# finalpcb_tz12_fp10.net
KiCad netlist of a schematic drawn in EAGLE
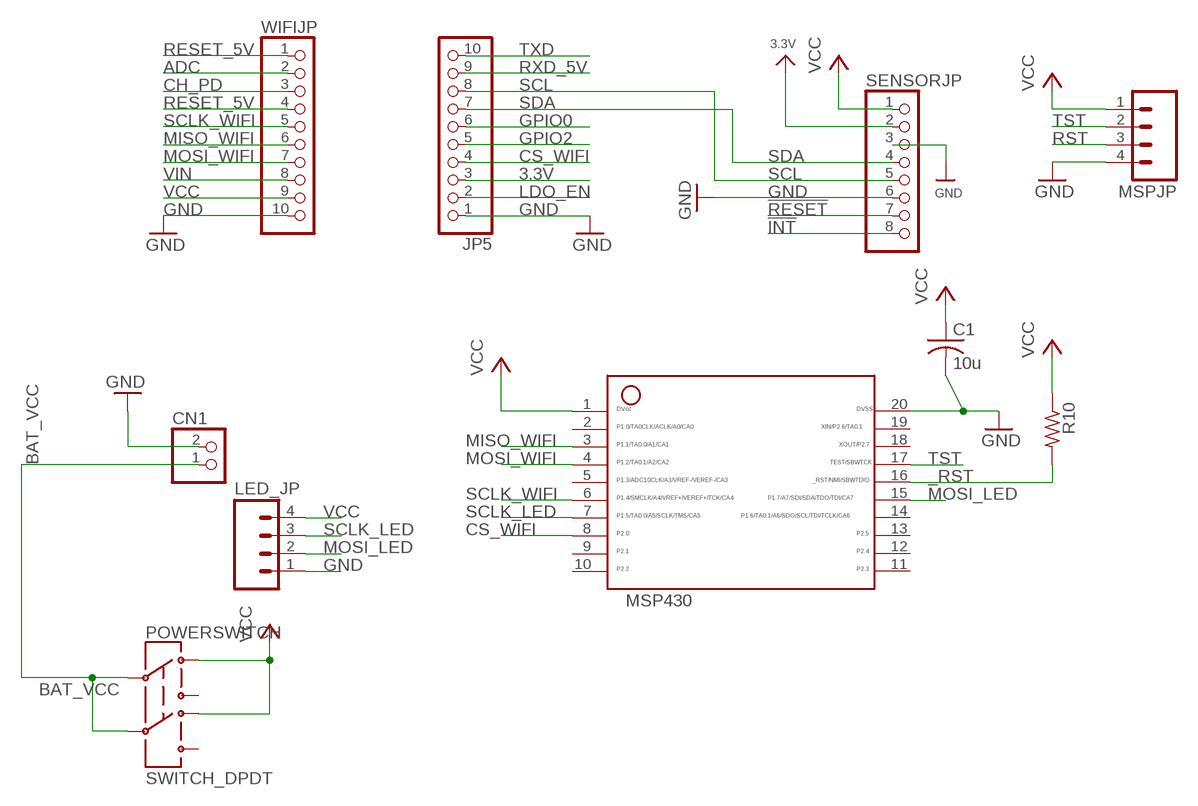
[diagram p0: schematic, sheet 1]

(export (version "E")
  (design (tool "Eeschema 10.0.6"))
  (components
    (comp (ref "C1")
      (value "10u")
      (footprint "eagle-import:C1206")
      (libsource (lib "eagle-import") (part "C-USC1206"))
    )
    (comp (ref "CN1")
      (value "JST_2PIN-SMT-RA")
      (footprint "eagle-import:JST-PH-2-SMT-RA")
      (libsource (lib "eagle-import") (part "JST_2PIN-SMT-RA"))
    )
    (comp (ref "JP5")
      (value "HEADER-1X1070MIL")
      (footprint "eagle-import:1X10_ROUND70")
      (libsource (lib "eagle-import") (part "HEADER-1X1070MIL"))
    )
    (comp (ref "LED_JP")
      (value "PENDANT_M04LOCK")
      (footprint "eagle-import:PENDANT_1X04_LOCK")
      (libsource (lib "eagle-import") (part "PENDANT_M04LOCK"))
    )
    (comp (ref "MSP430")
      (value "RATDBS_MSP430")
      (footprint "eagle-import:RATDBS_20_PIN")
      (libsource (lib "eagle-import") (part "RATDBS_MSP430"))
    )
    (comp (ref "MSPJP")
      (value "PENDANT_M04LOCK")
      (footprint "eagle-import:PENDANT_1X04_LOCK")
      (libsource (lib "eagle-import") (part "PENDANT_M04LOCK"))
    )
    (comp (ref "POWERSWITCH")
      (value "SWITCH_DPDT")
      (footprint "eagle-import:JS_DPDT_TH")
      (libsource (lib "eagle-import") (part "SWITCH_DPDT"))
    )
    (comp (ref "R10")
      (value "R-US_R1206")
      (footprint "eagle-import:R1206")
      (libsource (lib "eagle-import") (part "R-US_R1206"))
    )
    (comp (ref "SENSORJP")
      (value "HEADER-1X870MIL")
      (footprint "eagle-import:1X08_ROUND_70")
      (libsource (lib "eagle-import") (part "HEADER-1X870MIL"))
    )
    (comp (ref "WIFIJP")
      (value "HEADER-1X1070MIL")
      (footprint "eagle-import:1X10_ROUND70")
      (libsource (lib "eagle-import") (part "HEADER-1X1070MIL"))
    )
  )
  (nets
    (net (code "1") (name "/ADC") (class "Default")
      (node (ref "WIFIJP") (pin "2") (pinfunction "2_2") (pintype "passive"))
    )
    (net (code "2") (name "/BAT_VCC") (class "Default")
      (node (ref "CN1") (pin "1") (pinfunction "2_1") (pintype "passive"))
      (node (ref "POWERSWITCH") (pin "2") (pinfunction "2_2") (pintype "bidirectional"))
      (node (ref "POWERSWITCH") (pin "5") (pinfunction "5_5") (pintype "bidirectional"))
    )
    (net (code "3") (name "/CH_PD") (class "Default")
      (node (ref "WIFIJP") (pin "3") (pinfunction "3_3") (pintype "passive"))
    )
    (net (code "4") (name "/CS_WIFI") (class "Default")
      (node (ref "JP5") (pin "4") (pinfunction "4_4") (pintype "passive"))
      (node (ref "MSP430") (pin "8") (pinfunction "8_8") (pintype "bidirectional"))
    )
    (net (code "5") (name "/GPIO0") (class "Default")
      (node (ref "JP5") (pin "6") (pinfunction "6_6") (pintype "passive"))
    )
    (net (code "6") (name "/GPIO2") (class "Default")
      (node (ref "JP5") (pin "5") (pinfunction "5_5") (pintype "passive"))
    )
    (net (code "7") (name "/LDO_EN") (class "Default")
      (node (ref "JP5") (pin "2") (pinfunction "2_2") (pintype "passive"))
    )
    (net (code "8") (name "/MISO_WIFI") (class "Default")
      (node (ref "MSP430") (pin "3") (pinfunction "3_3") (pintype "bidirectional"))
      (node (ref "WIFIJP") (pin "6") (pinfunction "6_6") (pintype "passive"))
    )
    (net (code "9") (name "/MOSI_LED") (class "Default")
      (node (ref "LED_JP") (pin "2") (pinfunction "2_2") (pintype "passive"))
      (node (ref "MSP430") (pin "15") (pinfunction "15_15") (pintype "bidirectional"))
    )
    (net (code "10") (name "/MOSI_WIFI") (class "Default")
      (node (ref "MSP430") (pin "4") (pinfunction "4_4") (pintype "bidirectional"))
      (node (ref "WIFIJP") (pin "7") (pinfunction "7_7") (pintype "passive"))
    )
    (net (code "11") (name "/RESET_5V") (class "Default")
      (node (ref "WIFIJP") (pin "1") (pinfunction "1_1") (pintype "passive"))
      (node (ref "WIFIJP") (pin "4") (pinfunction "4_4") (pintype "passive"))
    )
    (net (code "12") (name "/RST") (class "Default")
      (node (ref "MSPJP") (pin "3") (pinfunction "3_3") (pintype "passive"))
    )
    (net (code "13") (name "/RXD_5V") (class "Default")
      (node (ref "JP5") (pin "9") (pinfunction "9_9") (pintype "passive"))
    )
    (net (code "14") (name "/SCL") (class "Default")
      (node (ref "JP5") (pin "8") (pinfunction "8_8") (pintype "passive"))
      (node (ref "SENSORJP") (pin "5") (pinfunction "5_5") (pintype "passive"))
    )
    (net (code "15") (name "/SCLK_LED") (class "Default")
      (node (ref "LED_JP") (pin "3") (pinfunction "3_3") (pintype "passive"))
      (node (ref "MSP430") (pin "7") (pinfunction "7_7") (pintype "bidirectional"))
    )
    (net (code "16") (name "/SCLK_WIFI") (class "Default")
      (node (ref "MSP430") (pin "6") (pinfunction "6_6") (pintype "bidirectional"))
      (node (ref "WIFIJP") (pin "5") (pinfunction "5_5") (pintype "passive"))
    )
    (net (code "17") (name "/SDA") (class "Default")
      (node (ref "JP5") (pin "7") (pinfunction "7_7") (pintype "passive"))
      (node (ref "SENSORJP") (pin "4") (pinfunction "4_4") (pintype "passive"))
    )
    (net (code "18") (name "/TST") (class "Default")
      (node (ref "MSP430") (pin "17") (pinfunction "17_17") (pintype "bidirectional"))
      (node (ref "MSPJP") (pin "2") (pinfunction "2_2") (pintype "passive"))
    )
    (net (code "19") (name "/TXD") (class "Default")
      (node (ref "JP5") (pin "10") (pinfunction "10_10") (pintype "passive"))
    )
    (net (code "20") (name "/VIN") (class "Default")
      (node (ref "WIFIJP") (pin "8") (pinfunction "8_8") (pintype "passive"))
    )
    (net (code "21") (name "/_RST") (class "Default")
      (node (ref "MSP430") (pin "16") (pinfunction "16_16") (pintype "bidirectional"))
      (node (ref "R10") (pin "2") (pinfunction "2_2") (pintype "passive"))
    )
    (net (code "22") (name "/~{INT}") (class "Default")
      (node (ref "SENSORJP") (pin "8") (pinfunction "8_8") (pintype "passive"))
    )
    (net (code "23") (name "/~{RESET}") (class "Default")
      (node (ref "SENSORJP") (pin "7") (pinfunction "7_7") (pintype "passive"))
    )
    (net (code "24") (name "3.3V") (class "Default")
      (node (ref "JP5") (pin "3") (pinfunction "3_3") (pintype "passive"))
      (node (ref "SENSORJP") (pin "2") (pinfunction "2_2") (pintype "passive"))
    )
    (net (code "25") (name "GND") (class "Default")
      (node (ref "C1") (pin "2") (pinfunction "2_2") (pintype "passive"))
      (node (ref "CN1") (pin "2") (pinfunction "1_2") (pintype "passive"))
      (node (ref "JP5") (pin "1") (pinfunction "1_1") (pintype "passive"))
      (node (ref "LED_JP") (pin "1") (pinfunction "1_1") (pintype "passive"))
      (node (ref "MSP430") (pin "20") (pinfunction "20_20") (pintype "bidirectional"))
      (node (ref "MSPJP") (pin "4") (pinfunction "4_4") (pintype "passive"))
      (node (ref "SENSORJP") (pin "3") (pinfunction "3_3") (pintype "passive"))
      (node (ref "SENSORJP") (pin "6") (pinfunction "6_6") (pintype "passive"))
      (node (ref "WIFIJP") (pin "10") (pinfunction "10_10") (pintype "passive"))
    )
    (net (code "26") (name "VCC") (class "Default")
      (node (ref "C1") (pin "1") (pinfunction "1_1") (pintype "passive"))
      (node (ref "LED_JP") (pin "4") (pinfunction "4_4") (pintype "passive"))
      (node (ref "MSP430") (pin "1") (pinfunction "1_1") (pintype "bidirectional"))
      (node (ref "MSPJP") (pin "1") (pinfunction "1_1") (pintype "passive"))
      (node (ref "POWERSWITCH") (pin "1") (pinfunction "1_1") (pintype "bidirectional"))
      (node (ref "POWERSWITCH") (pin "4") (pinfunction "4_4") (pintype "bidirectional"))
      (node (ref "R10") (pin "1") (pinfunction "1_1") (pintype "passive"))
      (node (ref "SENSORJP") (pin "1") (pinfunction "1_1") (pintype "passive"))
      (node (ref "WIFIJP") (pin "9") (pinfunction "9_9") (pintype "passive"))
    )
    (net (code "27") (name "unconnected-(MSP430-Pad2)") (class "Default")
      (node (ref "MSP430") (pin "2") (pinfunction "2_2") (pintype "bidirectional"))
    )
    (net (code "28") (name "unconnected-(MSP430-Pad5)") (class "Default")
      (node (ref "MSP430") (pin "5") (pinfunction "5_5") (pintype "bidirectional"))
    )
    (net (code "29") (name "unconnected-(MSP430-Pad9)") (class "Default")
      (node (ref "MSP430") (pin "9") (pinfunction "9_9") (pintype "bidirectional"))
    )
    (net (code "30") (name "unconnected-(MSP430-Pad10)") (class "Default")
      (node (ref "MSP430") (pin "10") (pinfunction "10_10") (pintype "bidirectional"))
    )
    (net (code "31") (name "unconnected-(MSP430-Pad11)") (class "Default")
      (node (ref "MSP430") (pin "11") (pinfunction "11_11") (pintype "bidirectional"))
    )
    (net (code "32") (name "unconnected-(MSP430-Pad12)") (class "Default")
      (node (ref "MSP430") (pin "12") (pinfunction "12_12") (pintype "bidirectional"))
    )
    (net (code "33") (name "unconnected-(MSP430-Pad13)") (class "Default")
      (node (ref "MSP430") (pin "13") (pinfunction "13_13") (pintype "bidirectional"))
    )
    (net (code "34") (name "unconnected-(MSP430-Pad14)") (class "Default")
      (node (ref "MSP430") (pin "14") (pinfunction "14_14") (pintype "bidirectional"))
    )
    (net (code "35") (name "unconnected-(MSP430-Pad18)") (class "Default")
      (node (ref "MSP430") (pin "18") (pinfunction "18_18") (pintype "bidirectional"))
    )
    (net (code "36") (name "unconnected-(MSP430-Pad19)") (class "Default")
      (node (ref "MSP430") (pin "19") (pinfunction "19_19") (pintype "bidirectional"))
    )
    (net (code "37") (name "unconnected-(POWERSWITCH-Pad3)") (class "Default")
      (node (ref "POWERSWITCH") (pin "3") (pinfunction "3_3") (pintype "bidirectional"))
    )
    (net (code "38") (name "unconnected-(POWERSWITCH-Pad6)") (class "Default")
      (node (ref "POWERSWITCH") (pin "6") (pinfunction "6_6") (pintype "bidirectional"))
    )
  )
)
